# Components.net
KiCad netlist of a schematic drawn in Altium Designer
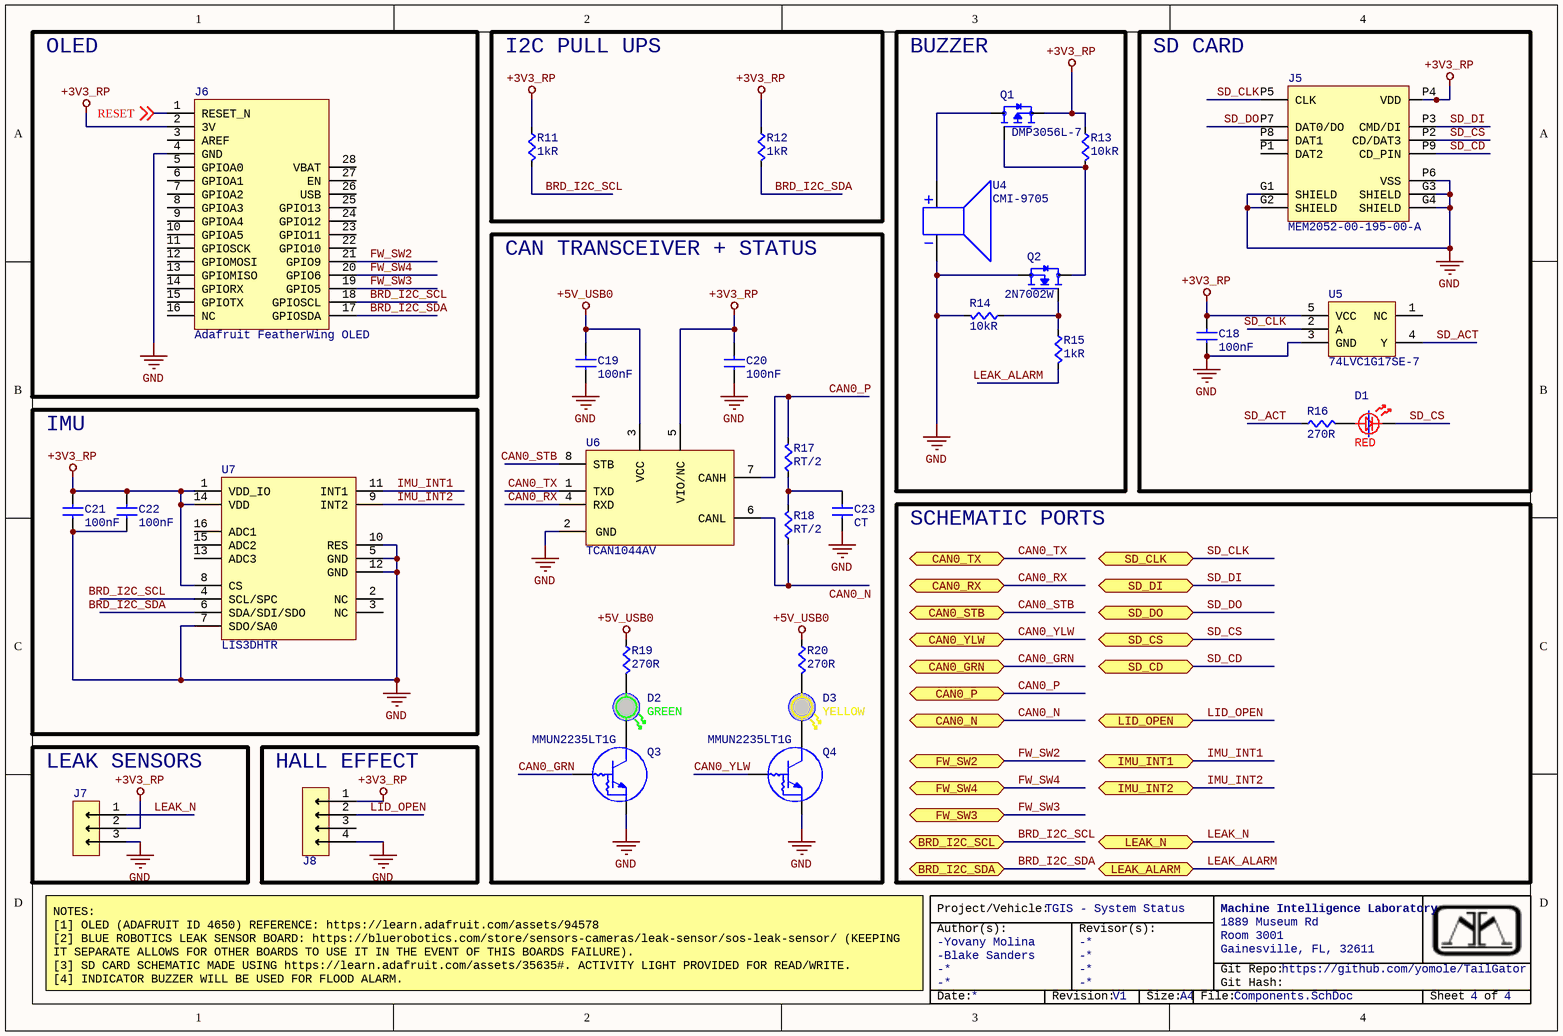
[diagram p0: Components.SchDoc]

(export (version "E")
  (design (tool "Eeschema 10.0.6"))
  (components
    (comp (ref "C18")
      (value "100nF")
      (footprint "CAPC0603")
      (description "Ceramic Capacitor, Multilayer, Cera")
      (fields (field (name "PART NUMBER") "CC0603KRX7R7BB104") (field (name "MANUFACTURER") "Yageo"))
      (libsource (lib "Parts") (part "NP_Capacitor"))
    )
    (comp (ref "C19")
      (value "100nF")
      (footprint "CAPC0603")
      (description "Ceramic Capacitor, Multilayer, Cera")
      (fields (field (name "PART NUMBER") "CC0603KRX7R7BB104") (field (name "MANUFACTURER") "Yageo"))
      (libsource (lib "Parts") (part "NP_Capacitor"))
    )
    (comp (ref "C20")
      (value "100nF")
      (footprint "CAPC0603")
      (description "Ceramic Capacitor, Multilayer, Cera")
      (fields (field (name "PART NUMBER") "CC0603KRX7R7BB104") (field (name "MANUFACTURER") "Yageo"))
      (libsource (lib "Parts") (part "NP_Capacitor"))
    )
    (comp (ref "C21")
      (value "100nF")
      (footprint "CAPC0603")
      (description "Ceramic Capacitor, Multilayer, Cera")
      (fields (field (name "PART NUMBER") "CC0603KRX7R7BB104") (field (name "MANUFACTURER") "Yageo"))
      (libsource (lib "Parts") (part "NP_Capacitor"))
    )
    (comp (ref "C22")
      (value "100nF")
      (footprint "CAPC0603")
      (description "Ceramic Capacitor, Multilayer, Cera")
      (fields (field (name "PART NUMBER") "CC0603KRX7R7BB104") (field (name "MANUFACTURER") "Yageo"))
      (libsource (lib "Parts") (part "NP_Capacitor"))
    )
    (comp (ref "C23")
      (value "CT")
      (footprint "CAPC0603")
      (fields (field (name "Comment") "Cap"))
      (libsource (lib "Passives") (part "Cap"))
    )
    (comp (ref "D1")
      (value "RED")
      (footprint "LED0603")
      (description "Single Color LED, Red, Water Clear,")
      (fields (field (name "PART NUMBER") "150060RS75000") (field (name "MANUFACTURER") "Wurth Electronics"))
      (libsource (lib "Parts") (part "LED_Red"))
    )
    (comp (ref "D2")
      (value "GREEN")
      (footprint "LED0603")
      (description "Single Color LED, Bright Green, Wat")
      (fields (field (name "PART NUMBER") "150060VS75000") (field (name "MANUFACTURER") "Wurth Electronics"))
      (libsource (lib "Parts") (part "LED_Green"))
    )
    (comp (ref "D3")
      (value "YELLOW")
      (footprint "LED0603")
      (description "Single Color LED, Yellow, Water Cle")
      (fields (field (name "PART NUMBER") "150060YS75000") (field (name "MANUFACTURER") "Wurth Electronics"))
      (libsource (lib "Parts") (part "LED_Yellow"))
    )
    (comp (ref "J5")
      (value "MEM2052-00-195-00-A")
      (footprint "GCT_MEM2052-00-195-00-A_REVA")
      (description "9 (8 + 1) Position Card Connector Secure Digital - microSD™ Surface Mount, Right Angle Gold")
      (libsource (lib "TGIS") (part "MEM2052-00-195-00-A"))
    )
    (comp (ref "J6")
      (value "Adafruit FeatherWing OLED")
      (footprint "ADAFRUIT_4650")
      (description "Adafruit FeatherWing OLED - 128x64 OLED Add-on For Feather - STEMMA QT / Qwiic")
      (libsource (lib "TGIS") (part "ADAFRUIT_4650"))
    )
    (comp (ref "J7")
      (value "0353630360")
      (footprint "MOLEX-HDR-1X3-SHERLOCK-RA")
      (description "Header, Molex, 2mm Pitch Sherlock Header, Single Row, Right Angle 3 Circuits, Length 3.3mm")
      (fields
        (field (name "MANUFACTURER PART NUMBER") "35363-0360")
        (field (name "MANUFACTURER") "Molex Connector Corporation")
      )
      (libsource (lib "Connectors") (part "SHERLOCK-1x3-RA"))
    )
    (comp (ref "J8")
      (value "0353630460")
      (footprint "MOLEX-HDR-1X4-SHERLOCK-RA")
      (description "Header, Molex, 2mm Pitch Sherlock Header, Single Row, Horizontal, 4 Circuits, Length 3.3mm")
      (fields (field (name "MANUFACTURER") "Molex"))
      (libsource (lib "Connectors") (part "SHERLOCK-1x4-RA"))
    )
    (comp (ref "Q1")
      (value "DMP3056L-7")
      (footprint "SOT-23-3")
      (description "Power Field-Effect Transistor, 4.3A")
      (fields (field (name "MANUFACTURER") "Diodes"))
      (libsource (lib "Parts") (part "PMOSFET"))
    )
    (comp (ref "Q2")
      (value "2N7002W")
      (footprint "SOT-323")
      (description "Small Signal Field-Effect Transisto")
      (fields (field (name "MANUFACTURER") "ON Semiconductor / Fairchild"))
      (libsource (lib "Parts") (part "NMOSFET"))
    )
    (comp (ref "Q3")
      (value "MMUN2235LT1G")
      (footprint "SOT-23-3")
      (description "Small Signal Bipolar Transistor, 0.")
      (fields (field (name "MANUFACTURER") "ON Semiconductor"))
      (libsource (lib "Parts") (part "PB_NPN_Transistor"))
    )
    (comp (ref "Q4")
      (value "MMUN2235LT1G")
      (footprint "SOT-23-3")
      (description "Small Signal Bipolar Transistor, 0.")
      (fields (field (name "MANUFACTURER") "ON Semiconductor"))
      (libsource (lib "Parts") (part "PB_NPN_Transistor"))
    )
    (comp (ref "R11")
      (value "1kR")
      (footprint "RES0603")
      (description "Fixed Resistor, Metal Glaze/thick F")
      (fields (field (name "PART NUMBER") "RC0603FR-071KL") (field (name "POWER") "100mW"))
      (libsource (lib "Parts") (part "Resistor"))
    )
    (comp (ref "R12")
      (value "1kR")
      (footprint "RES0603")
      (description "Fixed Resistor, Metal Glaze/thick F")
      (fields (field (name "PART NUMBER") "RC0603FR-071KL") (field (name "POWER") "100mW"))
      (libsource (lib "Parts") (part "Resistor"))
    )
    (comp (ref "R13")
      (value "10kR")
      (footprint "RES0603")
      (description "Fixed Resistor, Metal Glaze/thick F")
      (fields (field (name "PART NUMBER") "RC0603FR-0710KL") (field (name "POWER") "100mW"))
      (libsource (lib "Parts") (part "Resistor"))
    )
    (comp (ref "R14")
      (value "10kR")
      (footprint "RES0603")
      (description "Fixed Resistor, Metal Glaze/thick F")
      (fields (field (name "PART NUMBER") "RC0603FR-0710KL") (field (name "POWER") "100mW"))
      (libsource (lib "Parts") (part "Resistor"))
    )
    (comp (ref "R15")
      (value "1kR")
      (footprint "RES0603")
      (description "Fixed Resistor, Metal Glaze/thick F")
      (fields (field (name "PART NUMBER") "RC0603FR-071KL") (field (name "POWER") "100mW"))
      (libsource (lib "Parts") (part "Resistor"))
    )
    (comp (ref "R16")
      (value "270R")
      (footprint "RES0603")
      (description "Fixed Resistor, Metal Glaze/thick F")
      (fields (field (name "PART NUMBER") "RC0603FR-07270RL") (field (name "POWER") "100mW"))
      (libsource (lib "Parts") (part "Resistor"))
    )
    (comp (ref "R17")
      (value "RT/2")
      (footprint "RES0603")
      (fields (field (name "Comment") "Res"))
      (libsource (lib "Passives") (part "Res"))
    )
    (comp (ref "R18")
      (value "RT/2")
      (footprint "RES0603")
      (fields (field (name "Comment") "Res"))
      (libsource (lib "Passives") (part "Res"))
    )
    (comp (ref "R19")
      (value "270R")
      (footprint "RES0603")
      (description "Fixed Resistor, Metal Glaze/thick F")
      (fields (field (name "PART NUMBER") "RC0603FR-07270RL") (field (name "POWER") "100mW"))
      (libsource (lib "Parts") (part "Resistor"))
    )
    (comp (ref "R20")
      (value "270R")
      (footprint "RES0603")
      (description "Fixed Resistor, Metal Glaze/thick F")
      (fields (field (name "PART NUMBER") "RC0603FR-07270RL") (field (name "POWER") "100mW"))
      (libsource (lib "Parts") (part "Resistor"))
    )
    (comp (ref "U4")
      (value "CMI-9705")
      (footprint "CUI_CMI-9705-0380-SMT-TR")
      (libsource (lib "TGIS") (part "CMI-9705-0380-SMT-TR"))
    )
    (comp (ref "U5")
      (value "74LVC1G17SE-7")
      (footprint "SOT65P210X110-5N")
      (description "Buffer, Non-Inverting 1 Element 1 Bit per Element Push-Pull Output SOT-353")
      (libsource (lib "TGIS") (part "74LVC1G17SE-7"))
    )
    (comp (ref "U6")
      (value "TCAN1044AV")
      (footprint "SOT65P280X110-8N")
      (description "1/1 Transceiver Half CANbus TSOT-23-8")
      (libsource (lib "TGIS_Microcontrollers") (part "TCAN1044AVDDFRQ1"))
    )
    (comp (ref "U7")
      (value "LIS3DHTR")
      (footprint "XDCR_LIS3DHTR")
      (description "Accelerometer X, Y, Z Axis ±2g, 4g, 8g, 16g 0.5Hz ~ 625Hz 16-LGA (3x3)")
      (libsource (lib "TGIS") (part "LIS3DHTR"))
    )
  )
  (nets
    (net (code "1") (name "+3V3_RP") (class "Default")
      (node (ref "C18") (pin "1") (pinfunction "A_1") (pintype "passive"))
      (node (ref "C20") (pin "2") (pinfunction "B_2") (pintype "passive"))
      (node (ref "C21") (pin "2") (pinfunction "B_2") (pintype "passive"))
      (node (ref "C22") (pin "2") (pinfunction "B_2") (pintype "passive"))
      (node (ref "J5") (pin "P4") (pinfunction "VDD_P4") (pintype "passive"))
      (node (ref "J6") (pin "2") (pinfunction "3V_2") (pintype "passive"))
      (node (ref "J7") (pin "2") (pinfunction "2_2") (pintype "passive"))
      (node (ref "J8") (pin "1") (pinfunction "1_1") (pintype "passive"))
      (node (ref "Q1") (pin "2") (pinfunction "S_2") (pintype "passive"))
      (node (ref "R11") (pin "2") (pinfunction "B_2") (pintype "passive"))
      (node (ref "R12") (pin "2") (pinfunction "B_2") (pintype "passive"))
      (node (ref "R13") (pin "2") (pinfunction "B_2") (pintype "passive"))
      (node (ref "U5") (pin "5") (pinfunction "VCC_5") (pintype "passive"))
      (node (ref "U6") (pin "5") (pinfunction "VIO/NC_5") (pintype "passive"))
      (node (ref "U7") (pin "1") (pinfunction "VDD_IO_1") (pintype "passive"))
      (node (ref "U7") (pin "14") (pinfunction "VDD_14") (pintype "passive"))
      (node (ref "U7") (pin "8") (pinfunction "CS_8") (pintype "passive"))
    )
    (net (code "2") (name "+5V_USB0") (class "Default")
      (node (ref "C19") (pin "2") (pinfunction "B_2") (pintype "passive"))
      (node (ref "R19") (pin "2") (pinfunction "B_2") (pintype "passive"))
      (node (ref "R20") (pin "2") (pinfunction "B_2") (pintype "passive"))
      (node (ref "U6") (pin "3") (pinfunction "VCC_3") (pintype "passive"))
    )
    (net (code "3") (name "/BRD_I2C_SCL") (class "Default")
      (node (ref "J6") (pin "18") (pinfunction "GPIOSCL_18") (pintype "passive"))
      (node (ref "R11") (pin "1") (pinfunction "A_1") (pintype "passive"))
      (node (ref "U7") (pin "4") (pinfunction "SCL/SPC_4") (pintype "passive"))
    )
    (net (code "4") (name "/BRD_I2C_SDA") (class "Default")
      (node (ref "J6") (pin "17") (pinfunction "GPIOSDA_17") (pintype "passive"))
      (node (ref "R12") (pin "1") (pinfunction "A_1") (pintype "passive"))
      (node (ref "U7") (pin "6") (pinfunction "SDA/SDI/SDO_6") (pintype "passive"))
    )
    (net (code "5") (name "/CAN0_GRN") (class "Default")
      (node (ref "Q3") (pin "1") (pinfunction "B_1") (pintype "passive"))
    )
    (net (code "6") (name "/CAN0_N") (class "Default")
      (node (ref "R18") (pin "2") (pinfunction "B_2") (pintype "passive"))
      (node (ref "U6") (pin "6") (pinfunction "CANL_6") (pintype "passive"))
    )
    (net (code "7") (name "/CAN0_P") (class "Default")
      (node (ref "R17") (pin "1") (pinfunction "A_1") (pintype "passive"))
      (node (ref "U6") (pin "7") (pinfunction "CANH_7") (pintype "passive"))
    )
    (net (code "8") (name "/CAN0_RX") (class "Default")
      (node (ref "U6") (pin "4") (pinfunction "RXD_4") (pintype "passive"))
    )
    (net (code "9") (name "/CAN0_STB") (class "Default")
      (node (ref "U6") (pin "8") (pinfunction "STB_8") (pintype "passive"))
    )
    (net (code "10") (name "/CAN0_TX") (class "Default")
      (node (ref "U6") (pin "1") (pinfunction "TXD_1") (pintype "passive"))
    )
    (net (code "11") (name "/CAN0_YLW") (class "Default")
      (node (ref "Q4") (pin "1") (pinfunction "B_1") (pintype "passive"))
    )
    (net (code "12") (name "/FW_SW2") (class "Default")
      (node (ref "J6") (pin "21") (pinfunction "GPIO9_21") (pintype "passive"))
    )
    (net (code "13") (name "/FW_SW3") (class "Default")
      (node (ref "J6") (pin "19") (pinfunction "GPIO5_19") (pintype "passive"))
    )
    (net (code "14") (name "/FW_SW4") (class "Default")
      (node (ref "J6") (pin "20") (pinfunction "GPIO6_20") (pintype "passive"))
    )
    (net (code "15") (name "/IMU_INT1") (class "Default")
      (node (ref "U7") (pin "11") (pinfunction "INT1_11") (pintype "passive"))
    )
    (net (code "16") (name "/IMU_INT2") (class "Default")
      (node (ref "U7") (pin "9") (pinfunction "INT2_9") (pintype "passive"))
    )
    (net (code "17") (name "/LEAK_ALARM") (class "Default")
      (node (ref "R15") (pin "1") (pinfunction "A_1") (pintype "passive"))
    )
    (net (code "18") (name "/LEAK_N") (class "Default")
      (node (ref "J7") (pin "1") (pinfunction "1_1") (pintype "passive"))
    )
    (net (code "19") (name "/LID_OPEN") (class "Default")
      (node (ref "J8") (pin "2") (pinfunction "2_2") (pintype "passive"))
    )
    (net (code "20") (name "/SD_ACT") (class "Default")
      (node (ref "R16") (pin "2") (pinfunction "B_2") (pintype "passive"))
      (node (ref "U5") (pin "4") (pinfunction "Y_4") (pintype "passive"))
    )
    (net (code "21") (name "/SD_CD") (class "Default")
      (node (ref "J5") (pin "P9") (pinfunction "CD_PIN_P9") (pintype "passive"))
    )
    (net (code "22") (name "/SD_CLK") (class "Default")
      (node (ref "J5") (pin "P5") (pinfunction "CLK_P5") (pintype "passive"))
      (node (ref "U5") (pin "2") (pinfunction "A_2") (pintype "passive"))
    )
    (net (code "23") (name "/SD_CS") (class "Default")
      (node (ref "D1") (pin "C") (pinfunction "C_C") (pintype "passive"))
      (node (ref "J5") (pin "P2") (pinfunction "CD/DAT3_P2") (pintype "passive"))
    )
    (net (code "24") (name "/SD_DI") (class "Default")
      (node (ref "J5") (pin "P3") (pinfunction "CMD/DI_P3") (pintype "passive"))
    )
    (net (code "25") (name "/SD_DO") (class "Default")
      (node (ref "J5") (pin "P7") (pinfunction "DAT0/DO_P7") (pintype "passive"))
    )
    (net (code "26") (name "GND") (class "Default")
      (node (ref "C18") (pin "2") (pinfunction "B_2") (pintype "passive"))
      (node (ref "C19") (pin "1") (pinfunction "A_1") (pintype "passive"))
      (node (ref "C20") (pin "1") (pinfunction "A_1") (pintype "passive"))
      (node (ref "C21") (pin "1") (pinfunction "A_1") (pintype "passive"))
      (node (ref "C22") (pin "1") (pinfunction "A_1") (pintype "passive"))
      (node (ref "C23") (pin "2") (pinfunction "B_2") (pintype "passive"))
      (node (ref "J5") (pin "G1") (pinfunction "SHIELD_G1") (pintype "passive"))
      (node (ref "J5") (pin "G2") (pinfunction "SHIELD_G2") (pintype "passive"))
      (node (ref "J5") (pin "G3") (pinfunction "SHIELD_G3") (pintype "passive"))
      (node (ref "J5") (pin "G4") (pinfunction "SHIELD_G4") (pintype "passive"))
      (node (ref "J5") (pin "P6") (pinfunction "VSS_P6") (pintype "passive"))
      (node (ref "J6") (pin "4") (pinfunction "GND_4") (pintype "passive"))
      (node (ref "J7") (pin "3") (pinfunction "3_3") (pintype "passive"))
      (node (ref "J8") (pin "4") (pinfunction "4_4") (pintype "passive"))
      (node (ref "Q2") (pin "2") (pinfunction "S_2") (pintype "passive"))
      (node (ref "Q3") (pin "2") (pinfunction "E_2") (pintype "passive"))
      (node (ref "Q4") (pin "2") (pinfunction "E_2") (pintype "passive"))
      (node (ref "R14") (pin "1") (pinfunction "A_1") (pintype "passive"))
      (node (ref "U4") (pin "N") (pinfunction "N_N") (pintype "passive"))
      (node (ref "U5") (pin "3") (pinfunction "GND_3") (pintype "passive"))
      (node (ref "U6") (pin "2") (pinfunction "GND_2") (pintype "passive"))
      (node (ref "U7") (pin "10") (pinfunction "RES_10") (pintype "passive"))
      (node (ref "U7") (pin "12") (pinfunction "GND_12") (pintype "passive"))
      (node (ref "U7") (pin "5") (pinfunction "GND_5") (pintype "passive"))
      (node (ref "U7") (pin "7") (pinfunction "SDO/SA0_7") (pintype "passive"))
    )
    (net (code "27") (name "Net-(C23-A)") (class "Default")
      (node (ref "C23") (pin "1") (pinfunction "A_1") (pintype "passive"))
      (node (ref "R17") (pin "2") (pinfunction "B_2") (pintype "passive"))
      (node (ref "R18") (pin "1") (pinfunction "A_1") (pintype "passive"))
    )
    (net (code "28") (name "Net-(Q1-D)") (class "Default")
      (node (ref "Q1") (pin "3") (pinfunction "D_3") (pintype "passive"))
      (node (ref "U4") (pin "P") (pinfunction "P_P") (pintype "passive"))
    )
    (net (code "29") (name "Net-(Q1-G)") (class "Default")
      (node (ref "Q1") (pin "1") (pinfunction "G_1") (pintype "passive"))
      (node (ref "Q2") (pin "3") (pinfunction "D_3") (pintype "passive"))
      (node (ref "R13") (pin "1") (pinfunction "A_1") (pintype "passive"))
    )
    (net (code "30") (name "Net-(Q2-G)") (class "Default")
      (node (ref "Q2") (pin "1") (pinfunction "G_1") (pintype "passive"))
      (node (ref "R14") (pin "2") (pinfunction "B_2") (pintype "passive"))
      (node (ref "R15") (pin "2") (pinfunction "B_2") (pintype "passive"))
    )
    (net (code "31") (name "Net-(Q3-C)") (class "Default")
      (node (ref "D2") (pin "C") (pinfunction "C_C") (pintype "passive"))
      (node (ref "Q3") (pin "3") (pinfunction "C_3") (pintype "passive"))
    )
    (net (code "32") (name "Net-(Q4-C)") (class "Default")
      (node (ref "D3") (pin "C") (pinfunction "C_C") (pintype "passive"))
      (node (ref "Q4") (pin "3") (pinfunction "C_3") (pintype "passive"))
    )
    (net (code "33") (name "Net-(R16-A)") (class "Default")
      (node (ref "D1") (pin "A") (pinfunction "A_A") (pintype "passive"))
      (node (ref "R16") (pin "1") (pinfunction "A_1") (pintype "passive"))
    )
    (net (code "34") (name "Net-(R19-A)") (class "Default")
      (node (ref "D2") (pin "A") (pinfunction "A_A") (pintype "passive"))
      (node (ref "R19") (pin "1") (pinfunction "A_1") (pintype "passive"))
    )
    (net (code "35") (name "Net-(R20-A)") (class "Default")
      (node (ref "D3") (pin "A") (pinfunction "A_A") (pintype "passive"))
      (node (ref "R20") (pin "1") (pinfunction "A_1") (pintype "passive"))
    )
    (net (code "36") (name "RESET") (class "Default")
      (node (ref "J6") (pin "1") (pinfunction "RESET_N_1") (pintype "passive"))
    )
    (net (code "37") (name "unconnected-(J5-DAT1-PadP8)") (class "Default")
      (node (ref "J5") (pin "P8") (pinfunction "DAT1_P8") (pintype "passive"))
    )
    (net (code "38") (name "unconnected-(J5-DAT2-PadP1)") (class "Default")
      (node (ref "J5") (pin "P1") (pinfunction "DAT2_P1") (pintype "passive"))
    )
    (net (code "39") (name "unconnected-(J6-AREF-Pad3)") (class "Default")
      (node (ref "J6") (pin "3") (pinfunction "AREF_3") (pintype "passive"))
    )
    (net (code "40") (name "unconnected-(J6-EN-Pad27)") (class "Default")
      (node (ref "J6") (pin "27") (pinfunction "EN_27") (pintype "passive"))
    )
    (net (code "41") (name "unconnected-(J6-GPIO10-Pad22)") (class "Default")
      (node (ref "J6") (pin "22") (pinfunction "GPIO10_22") (pintype "passive"))
    )
    (net (code "42") (name "unconnected-(J6-GPIO11-Pad23)") (class "Default")
      (node (ref "J6") (pin "23") (pinfunction "GPIO11_23") (pintype "passive"))
    )
    (net (code "43") (name "unconnected-(J6-GPIO12-Pad24)") (class "Default")
      (node (ref "J6") (pin "24") (pinfunction "GPIO12_24") (pintype "passive"))
    )
    (net (code "44") (name "unconnected-(J6-GPIO13-Pad25)") (class "Default")
      (node (ref "J6") (pin "25") (pinfunction "GPIO13_25") (pintype "passive"))
    )
    (net (code "45") (name "unconnected-(J6-GPIOA0-Pad5)") (class "Default")
      (node (ref "J6") (pin "5") (pinfunction "GPIOA0_5") (pintype "passive"))
    )
    (net (code "46") (name "unconnected-(J6-GPIOA1-Pad6)") (class "Default")
      (node (ref "J6") (pin "6") (pinfunction "GPIOA1_6") (pintype "passive"))
    )
    (net (code "47") (name "unconnected-(J6-GPIOA2-Pad7)") (class "Default")
      (node (ref "J6") (pin "7") (pinfunction "GPIOA2_7") (pintype "passive"))
    )
    (net (code "48") (name "unconnected-(J6-GPIOA3-Pad8)") (class "Default")
      (node (ref "J6") (pin "8") (pinfunction "GPIOA3_8") (pintype "passive"))
    )
    (net (code "49") (name "unconnected-(J6-GPIOA4-Pad9)") (class "Default")
      (node (ref "J6") (pin "9") (pinfunction "GPIOA4_9") (pintype "passive"))
    )
    (net (code "50") (name "unconnected-(J6-GPIOA5-Pad10)") (class "Default")
      (node (ref "J6") (pin "10") (pinfunction "GPIOA5_10") (pintype "passive"))
    )
    (net (code "51") (name "unconnected-(J6-GPIOMISO-Pad13)") (class "Default")
      (node (ref "J6") (pin "13") (pinfunction "GPIOMISO_13") (pintype "passive"))
    )
    (net (code "52") (name "unconnected-(J6-GPIOMOSI-Pad12)") (class "Default")
      (node (ref "J6") (pin "12") (pinfunction "GPIOMOSI_12") (pintype "passive"))
    )
    (net (code "53") (name "unconnected-(J6-GPIORX-Pad14)") (class "Default")
      (node (ref "J6") (pin "14") (pinfunction "GPIORX_14") (pintype "passive"))
    )
    (net (code "54") (name "unconnected-(J6-GPIOSCK-Pad11)") (class "Default")
      (node (ref "J6") (pin "11") (pinfunction "GPIOSCK_11") (pintype "passive"))
    )
    (net (code "55") (name "unconnected-(J6-GPIOTX-Pad15)") (class "Default")
      (node (ref "J6") (pin "15") (pinfunction "GPIOTX_15") (pintype "passive"))
    )
    (net (code "56") (name "unconnected-(J6-NC-Pad16)") (class "Default")
      (node (ref "J6") (pin "16") (pinfunction "NC_16") (pintype "passive"))
    )
    (net (code "57") (name "unconnected-(J6-USB-Pad26)") (class "Default")
      (node (ref "J6") (pin "26") (pinfunction "USB_26") (pintype "passive"))
    )
    (net (code "58") (name "unconnected-(J6-VBAT-Pad28)") (class "Default")
      (node (ref "J6") (pin "28") (pinfunction "VBAT_28") (pintype "passive"))
    )
    (net (code "59") (name "unconnected-(J8-Pad3)") (class "Default")
      (node (ref "J8") (pin "3") (pinfunction "3_3") (pintype "passive"))
    )
    (net (code "60") (name "unconnected-(U5-NC-Pad1)") (class "Default")
      (node (ref "U5") (pin "1") (pinfunction "NC_1") (pintype "passive"))
    )
    (net (code "61") (name "unconnected-(U7-ADC1-Pad16)") (class "Default")
      (node (ref "U7") (pin "16") (pinfunction "ADC1_16") (pintype "passive"))
    )
    (net (code "62") (name "unconnected-(U7-ADC2-Pad15)") (class "Default")
      (node (ref "U7") (pin "15") (pinfunction "ADC2_15") (pintype "passive"))
    )
    (net (code "63") (name "unconnected-(U7-ADC3-Pad13)") (class "Default")
      (node (ref "U7") (pin "13") (pinfunction "ADC3_13") (pintype "passive"))
    )
    (net (code "64") (name "unconnected-(U7-NC-Pad2)") (class "Default")
      (node (ref "U7") (pin "2") (pinfunction "NC_2") (pintype "passive"))
    )
    (net (code "65") (name "unconnected-(U7-NC-Pad3)") (class "Default")
      (node (ref "U7") (pin "3") (pinfunction "NC_3") (pintype "passive"))
    )
  )
)
